# basic_micro.net
KiCad netlist of a schematic drawn in EAGLE
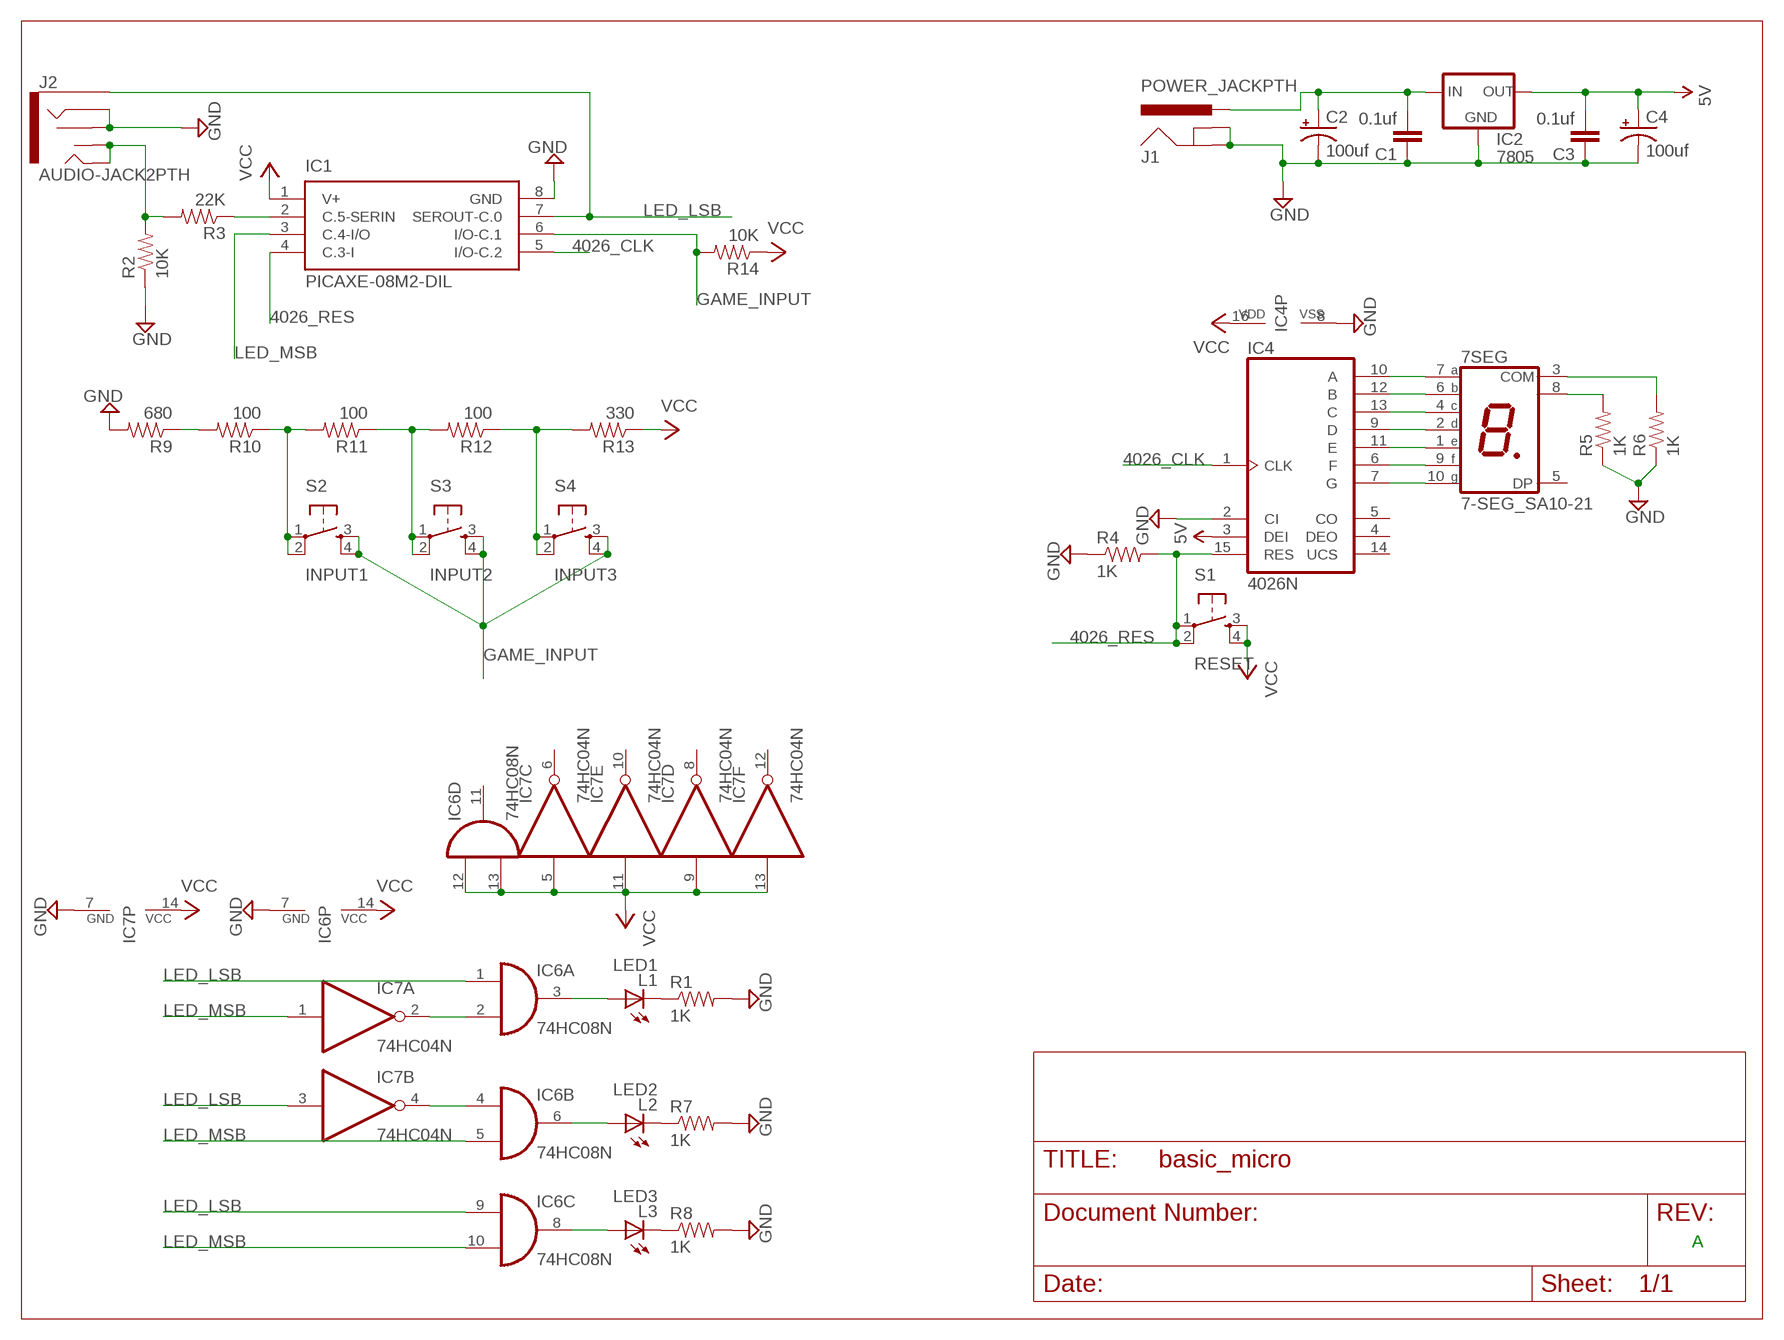
[diagram p0: schematic, sheet 1]

(export (version "E")
  (design (tool "Eeschema 10.0.6"))
  (components
    (comp (ref "7SEG")
      (value "7-SEG_SA10-21")
      (footprint "eagle-import:SA10-21")
      (libsource (lib "eagle-import") (part "7-SEG_SA10-21"))
    )
    (comp (ref "C1")
      (value "0.1uf")
      (footprint "eagle-import:C025-025X050")
      (libsource (lib "eagle-import") (part "C-EU025-025X050"))
    )
    (comp (ref "C2")
      (value "100uf")
      (footprint "eagle-import:ETR3")
      (libsource (lib "eagle-import") (part "CPOL-USETR3"))
    )
    (comp (ref "C3")
      (value "0.1uf")
      (footprint "eagle-import:C025-025X050")
      (libsource (lib "eagle-import") (part "C-EU025-025X050"))
    )
    (comp (ref "C4")
      (value "100uf")
      (footprint "eagle-import:ETR3")
      (libsource (lib "eagle-import") (part "CPOL-USETR3"))
    )
    (comp (ref "IC1")
      (value "PICAXE-08M2-DIL")
      (footprint "eagle-import:DIL8")
      (libsource (lib "eagle-import") (part "PICAXE-08M2-DIL"))
    )
    (comp (ref "IC2")
      (value "7805")
      (footprint "eagle-import:78XXL")
      (libsource (lib "eagle-import") (part "78XXL"))
    )
    (comp (ref "IC4")
      (value "4026N")
      (footprint "eagle-import:DIL16")
      (libsource (lib "eagle-import") (part "4026N"))
    )
    (comp (ref "IC6")
      (value "74HC08N")
      (footprint "eagle-import:DIL14")
      (libsource (lib "eagle-import") (part "7408NHC"))
    )
    (comp (ref "IC7")
      (value "74HC04N")
      (footprint "eagle-import:DIL14")
      (libsource (lib "eagle-import") (part "7404NHC"))
    )
    (comp (ref "J1")
      (value "POWER_JACKPTH")
      (footprint "eagle-import:POWER_JACK_PTH")
      (libsource (lib "eagle-import") (part "POWER_JACKPTH"))
    )
    (comp (ref "J2")
      (value "AUDIO-JACK2PTH")
      (footprint "eagle-import:AUDIO-JACK")
      (libsource (lib "eagle-import") (part "AUDIO-JACK2PTH"))
    )
    (comp (ref "L1")
      (value "LED1")
      (footprint "eagle-import:LED3MM")
      (libsource (lib "eagle-import") (part "LED3MM"))
    )
    (comp (ref "L2")
      (value "LED2")
      (footprint "eagle-import:LED3MM")
      (libsource (lib "eagle-import") (part "LED3MM"))
    )
    (comp (ref "L3")
      (value "LED3")
      (footprint "eagle-import:LED3MM")
      (libsource (lib "eagle-import") (part "LED3MM"))
    )
    (comp (ref "R1")
      (value "1K")
      (footprint "eagle-import:AXIAL-0.4")
      (libsource (lib "eagle-import") (part "RESISTORPTH-1/4W"))
    )
    (comp (ref "R2")
      (value "10K")
      (footprint "eagle-import:AXIAL-0.4")
      (libsource (lib "eagle-import") (part "RESISTORPTH-1/4W"))
    )
    (comp (ref "R3")
      (value "22K")
      (footprint "eagle-import:AXIAL-0.4")
      (libsource (lib "eagle-import") (part "RESISTORPTH-1/4W"))
    )
    (comp (ref "R4")
      (value "1K")
      (footprint "eagle-import:AXIAL-0.4")
      (libsource (lib "eagle-import") (part "RESISTORPTH-1/4W"))
    )
    (comp (ref "R5")
      (value "1K")
      (footprint "eagle-import:AXIAL-0.4")
      (libsource (lib "eagle-import") (part "RESISTORPTH-1/4W"))
    )
    (comp (ref "R6")
      (value "1K")
      (footprint "eagle-import:AXIAL-0.4")
      (libsource (lib "eagle-import") (part "RESISTORPTH-1/4W"))
    )
    (comp (ref "R7")
      (value "1K")
      (footprint "eagle-import:AXIAL-0.4")
      (libsource (lib "eagle-import") (part "RESISTORPTH-1/4W"))
    )
    (comp (ref "R8")
      (value "1K")
      (footprint "eagle-import:AXIAL-0.4")
      (libsource (lib "eagle-import") (part "RESISTORPTH-1/4W"))
    )
    (comp (ref "R9")
      (value "680")
      (footprint "eagle-import:AXIAL-0.4")
      (libsource (lib "eagle-import") (part "RESISTORPTH-1/4W"))
    )
    (comp (ref "R10")
      (value "100")
      (footprint "eagle-import:AXIAL-0.4")
      (libsource (lib "eagle-import") (part "RESISTORPTH-1/4W"))
    )
    (comp (ref "R11")
      (value "100")
      (footprint "eagle-import:AXIAL-0.4")
      (libsource (lib "eagle-import") (part "RESISTORPTH-1/4W"))
    )
    (comp (ref "R12")
      (value "100")
      (footprint "eagle-import:AXIAL-0.4")
      (libsource (lib "eagle-import") (part "RESISTORPTH-1/4W"))
    )
    (comp (ref "R13")
      (value "330")
      (footprint "eagle-import:AXIAL-0.4")
      (libsource (lib "eagle-import") (part "RESISTORPTH-1/4W"))
    )
    (comp (ref "R14")
      (value "10K")
      (footprint "eagle-import:AXIAL-0.4")
      (libsource (lib "eagle-import") (part "RESISTORPTH-1/4W"))
    )
    (comp (ref "S1")
      (value "RESET")
      (footprint "eagle-import:TACTILE-PTH")
      (libsource (lib "eagle-import") (part "TAC_SWITCHPTH"))
    )
    (comp (ref "S2")
      (value "INPUT1")
      (footprint "eagle-import:TACTILE-PTH")
      (libsource (lib "eagle-import") (part "TAC_SWITCHPTH"))
    )
    (comp (ref "S3")
      (value "INPUT2")
      (footprint "eagle-import:TACTILE-PTH")
      (libsource (lib "eagle-import") (part "TAC_SWITCHPTH"))
    )
    (comp (ref "S4")
      (value "INPUT3")
      (footprint "eagle-import:TACTILE-PTH")
      (libsource (lib "eagle-import") (part "TAC_SWITCHPTH"))
    )
  )
  (nets
    (net (code "1") (name "/4026_CLK") (class "Default")
      (node (ref "IC1") (pin "5") (pinfunction "I/O-C.2_5") (pintype "bidirectional"))
      (node (ref "IC4") (pin "1") (pinfunction "CLK_1") (pintype "input"))
    )
    (net (code "2") (name "/4026_RES") (class "Default")
      (node (ref "IC1") (pin "4") (pinfunction "C.3-I_4") (pintype "input"))
      (node (ref "IC4") (pin "15") (pinfunction "RES_15") (pintype "input"))
      (node (ref "R4") (pin "P$2") (pinfunction "2_P$2") (pintype "passive"))
      (node (ref "S1") (pin "1") (pinfunction "1_1") (pintype "passive"))
      (node (ref "S1") (pin "2") (pinfunction "2_2") (pintype "passive"))
    )
    (net (code "3") (name "/GAME_INPUT") (class "Default")
      (node (ref "IC1") (pin "6") (pinfunction "I/O-C.1_6") (pintype "bidirectional"))
      (node (ref "R14") (pin "P$2") (pinfunction "2_P$2") (pintype "passive"))
      (node (ref "S2") (pin "3") (pinfunction "3_3") (pintype "passive"))
      (node (ref "S2") (pin "4") (pinfunction "4_4") (pintype "passive"))
      (node (ref "S3") (pin "3") (pinfunction "3_3") (pintype "passive"))
      (node (ref "S3") (pin "4") (pinfunction "4_4") (pintype "passive"))
      (node (ref "S4") (pin "3") (pinfunction "3_3") (pintype "passive"))
      (node (ref "S4") (pin "4") (pinfunction "4_4") (pintype "passive"))
    )
    (net (code "4") (name "/LED_LSB") (class "Default")
      (node (ref "IC1") (pin "7") (pinfunction "SEROUT-C.0_7") (pintype "output"))
      (node (ref "IC6") (pin "1") (pinfunction "I0_1") (pintype "input"))
      (node (ref "IC6") (pin "9") (pinfunction "I0_9") (pintype "input"))
      (node (ref "IC7") (pin "3") (pinfunction "I_3") (pintype "input"))
      (node (ref "J2") (pin "SLEEVE") (pinfunction "SLEEVE_SLEEVE") (pintype "bidirectional"))
    )
    (net (code "5") (name "/LED_MSB") (class "Default")
      (node (ref "IC1") (pin "3") (pinfunction "C.4-I/O_3") (pintype "bidirectional"))
      (node (ref "IC6") (pin "10") (pinfunction "I1_10") (pintype "input"))
      (node (ref "IC6") (pin "5") (pinfunction "I1_5") (pintype "input"))
      (node (ref "IC7") (pin "1") (pinfunction "I_1") (pintype "input"))
    )
    (net (code "6") (name "5V") (class "Default")
      (node (ref "C3") (pin "2") (pinfunction "2_2") (pintype "passive"))
      (node (ref "C4") (pin "+") (pinfunction "+_+") (pintype "passive"))
      (node (ref "IC2") (pin "OUT") (pinfunction "OUT_OUT") (pintype "passive"))
      (node (ref "IC4") (pin "3") (pinfunction "DEI_3") (pintype "input"))
    )
    (net (code "7") (name "GND") (class "Default")
      (node (ref "C1") (pin "1") (pinfunction "1_1") (pintype "passive"))
      (node (ref "C2") (pin "-") (pinfunction "-_-") (pintype "passive"))
      (node (ref "C3") (pin "1") (pinfunction "1_1") (pintype "passive"))
      (node (ref "C4") (pin "-") (pinfunction "-_-") (pintype "passive"))
      (node (ref "IC1") (pin "8") (pinfunction "GND_8") (pintype "power_in"))
      (node (ref "IC2") (pin "GND") (pinfunction "GND_GND") (pintype "input"))
      (node (ref "IC4") (pin "2") (pinfunction "CI_2") (pintype "input"))
      (node (ref "IC4") (pin "8") (pinfunction "VSS_8") (pintype "power_in"))
      (node (ref "IC6") (pin "7") (pinfunction "GND_7") (pintype "power_in"))
      (node (ref "IC7") (pin "7") (pinfunction "GND_7") (pintype "power_in"))
      (node (ref "J1") (pin "GND") (pinfunction "GND_GND") (pintype "bidirectional"))
      (node (ref "J1") (pin "GNDBREAK") (pinfunction "GNDBREAK_GNDBREAK") (pintype "bidirectional"))
      (node (ref "J2") (pin "RING") (pinfunction "RING_RING") (pintype "bidirectional"))
      (node (ref "J2") (pin "RSH") (pinfunction "RSH_RSH") (pintype "bidirectional"))
      (node (ref "R1") (pin "P$2") (pinfunction "2_P$2") (pintype "passive"))
      (node (ref "R2") (pin "P$1") (pinfunction "1_P$1") (pintype "passive"))
      (node (ref "R4") (pin "P$1") (pinfunction "1_P$1") (pintype "passive"))
      (node (ref "R5") (pin "P$1") (pinfunction "1_P$1") (pintype "passive"))
      (node (ref "R6") (pin "P$1") (pinfunction "1_P$1") (pintype "passive"))
      (node (ref "R7") (pin "P$2") (pinfunction "2_P$2") (pintype "passive"))
      (node (ref "R8") (pin "P$2") (pinfunction "2_P$2") (pintype "passive"))
      (node (ref "R9") (pin "P$2") (pinfunction "2_P$2") (pintype "passive"))
    )
    (net (code "8") (name "Net-(7SEG-A)") (class "Default")
      (node (ref "7SEG") (pin "7") (pinfunction "A_7") (pintype "passive"))
      (node (ref "IC4") (pin "10") (pinfunction "A_10") (pintype "output"))
    )
    (net (code "9") (name "Net-(7SEG-B)") (class "Default")
      (node (ref "7SEG") (pin "6") (pinfunction "B_6") (pintype "passive"))
      (node (ref "IC4") (pin "12") (pinfunction "B_12") (pintype "output"))
    )
    (net (code "10") (name "Net-(7SEG-C)") (class "Default")
      (node (ref "7SEG") (pin "4") (pinfunction "C_4") (pintype "passive"))
      (node (ref "IC4") (pin "13") (pinfunction "C_13") (pintype "output"))
    )
    (net (code "11") (name "Net-(7SEG-D)") (class "Default")
      (node (ref "7SEG") (pin "2") (pinfunction "D_2") (pintype "passive"))
      (node (ref "IC4") (pin "9") (pinfunction "D_9") (pintype "output"))
    )
    (net (code "12") (name "Net-(7SEG-E)") (class "Default")
      (node (ref "7SEG") (pin "1") (pinfunction "E_1") (pintype "passive"))
      (node (ref "IC4") (pin "11") (pinfunction "E_11") (pintype "output"))
    )
    (net (code "13") (name "Net-(7SEG-F)") (class "Default")
      (node (ref "7SEG") (pin "9") (pinfunction "F_9") (pintype "passive"))
      (node (ref "IC4") (pin "6") (pinfunction "F_6") (pintype "output"))
    )
    (net (code "14") (name "Net-(7SEG-G)") (class "Default")
      (node (ref "7SEG") (pin "10") (pinfunction "G_10") (pintype "passive"))
      (node (ref "IC4") (pin "7") (pinfunction "G_7") (pintype "output"))
    )
    (net (code "15") (name "Net-(C1-Pad2)") (class "Default")
      (node (ref "C1") (pin "2") (pinfunction "2_2") (pintype "passive"))
      (node (ref "C2") (pin "+") (pinfunction "+_+") (pintype "passive"))
      (node (ref "IC2") (pin "IN") (pinfunction "IN_IN") (pintype "input"))
      (node (ref "J1") (pin "PWR") (pinfunction "PWR_PWR") (pintype "bidirectional"))
    )
    (net (code "16") (name "Net-(IC1-C.5-SERIN)") (class "Default")
      (node (ref "IC1") (pin "2") (pinfunction "C.5-SERIN_2") (pintype "input"))
      (node (ref "R3") (pin "P$1") (pinfunction "1_P$1") (pintype "passive"))
    )
    (net (code "17") (name "Net-(IC6A-I1)") (class "Default")
      (node (ref "IC6") (pin "2") (pinfunction "I1_2") (pintype "input"))
      (node (ref "IC7") (pin "2") (pinfunction "O_2") (pintype "output"))
    )
    (net (code "18") (name "Net-(IC6A-O)") (class "Default")
      (node (ref "IC6") (pin "3") (pinfunction "O_3") (pintype "output"))
      (node (ref "L1") (pin "A") (pinfunction "A_A") (pintype "passive"))
    )
    (net (code "19") (name "Net-(IC6B-I0)") (class "Default")
      (node (ref "IC6") (pin "4") (pinfunction "I0_4") (pintype "input"))
      (node (ref "IC7") (pin "4") (pinfunction "O_4") (pintype "output"))
    )
    (net (code "20") (name "Net-(IC6B-O)") (class "Default")
      (node (ref "IC6") (pin "6") (pinfunction "O_6") (pintype "output"))
      (node (ref "L2") (pin "A") (pinfunction "A_A") (pintype "passive"))
    )
    (net (code "21") (name "Net-(IC6C-O)") (class "Default")
      (node (ref "IC6") (pin "8") (pinfunction "O_8") (pintype "output"))
      (node (ref "L3") (pin "A") (pinfunction "A_A") (pintype "passive"))
    )
    (net (code "22") (name "Net-(L1-C)") (class "Default")
      (node (ref "L1") (pin "K") (pinfunction "C_K") (pintype "passive"))
      (node (ref "R1") (pin "P$1") (pinfunction "1_P$1") (pintype "passive"))
    )
    (net (code "23") (name "Net-(L2-C)") (class "Default")
      (node (ref "L2") (pin "K") (pinfunction "C_K") (pintype "passive"))
      (node (ref "R7") (pin "P$1") (pinfunction "1_P$1") (pintype "passive"))
    )
    (net (code "24") (name "Net-(L3-C)") (class "Default")
      (node (ref "L3") (pin "K") (pinfunction "C_K") (pintype "passive"))
      (node (ref "R8") (pin "P$1") (pinfunction "1_P$1") (pintype "passive"))
    )
    (net (code "25") (name "Net-(R2-2)") (class "Default")
      (node (ref "J2") (pin "TIP") (pinfunction "TIP_TIP") (pintype "bidirectional"))
      (node (ref "J2") (pin "TSH") (pinfunction "TSH_TSH") (pintype "bidirectional"))
      (node (ref "R2") (pin "P$2") (pinfunction "2_P$2") (pintype "passive"))
      (node (ref "R3") (pin "P$2") (pinfunction "2_P$2") (pintype "passive"))
    )
    (net (code "26") (name "Net-(R5-2)") (class "Default")
      (node (ref "7SEG") (pin "8") (pinfunction "COM_8") (pintype "passive"))
      (node (ref "R5") (pin "P$2") (pinfunction "2_P$2") (pintype "passive"))
    )
    (net (code "27") (name "Net-(R6-2)") (class "Default")
      (node (ref "7SEG") (pin "3") (pinfunction "COM_3") (pintype "passive"))
      (node (ref "R6") (pin "P$2") (pinfunction "2_P$2") (pintype "passive"))
    )
    (net (code "28") (name "Net-(R10-1)") (class "Default")
      (node (ref "R10") (pin "P$1") (pinfunction "1_P$1") (pintype "passive"))
      (node (ref "R11") (pin "P$2") (pinfunction "2_P$2") (pintype "passive"))
      (node (ref "S2") (pin "1") (pinfunction "1_1") (pintype "passive"))
      (node (ref "S2") (pin "2") (pinfunction "2_2") (pintype "passive"))
    )
    (net (code "29") (name "Net-(R10-2)") (class "Default")
      (node (ref "R10") (pin "P$2") (pinfunction "2_P$2") (pintype "passive"))
      (node (ref "R9") (pin "P$1") (pinfunction "1_P$1") (pintype "passive"))
    )
    (net (code "30") (name "Net-(R11-1)") (class "Default")
      (node (ref "R11") (pin "P$1") (pinfunction "1_P$1") (pintype "passive"))
      (node (ref "R12") (pin "P$2") (pinfunction "2_P$2") (pintype "passive"))
      (node (ref "S3") (pin "1") (pinfunction "1_1") (pintype "passive"))
      (node (ref "S3") (pin "2") (pinfunction "2_2") (pintype "passive"))
    )
    (net (code "31") (name "Net-(R12-1)") (class "Default")
      (node (ref "R12") (pin "P$1") (pinfunction "1_P$1") (pintype "passive"))
      (node (ref "R13") (pin "P$2") (pinfunction "2_P$2") (pintype "passive"))
      (node (ref "S4") (pin "1") (pinfunction "1_1") (pintype "passive"))
      (node (ref "S4") (pin "2") (pinfunction "2_2") (pintype "passive"))
    )
    (net (code "32") (name "VCC") (class "Default")
      (node (ref "IC1") (pin "1") (pinfunction "V+_1") (pintype "power_in"))
      (node (ref "IC4") (pin "16") (pinfunction "VDD_16") (pintype "power_in"))
      (node (ref "IC6") (pin "12") (pinfunction "I0_12") (pintype "input"))
      (node (ref "IC6") (pin "13") (pinfunction "I1_13") (pintype "input"))
      (node (ref "IC6") (pin "14") (pinfunction "VCC_14") (pintype "power_in"))
      (node (ref "IC7") (pin "11") (pinfunction "I_11") (pintype "input"))
      (node (ref "IC7") (pin "13") (pinfunction "I_13") (pintype "input"))
      (node (ref "IC7") (pin "14") (pinfunction "VCC_14") (pintype "power_in"))
      (node (ref "IC7") (pin "5") (pinfunction "I_5") (pintype "input"))
      (node (ref "IC7") (pin "9") (pinfunction "I_9") (pintype "input"))
      (node (ref "R13") (pin "P$1") (pinfunction "1_P$1") (pintype "passive"))
      (node (ref "R14") (pin "P$1") (pinfunction "1_P$1") (pintype "passive"))
      (node (ref "S1") (pin "3") (pinfunction "3_3") (pintype "passive"))
      (node (ref "S1") (pin "4") (pinfunction "4_4") (pintype "passive"))
    )
    (net (code "33") (name "unconnected-(7SEG-DP-Pad5)") (class "Default")
      (node (ref "7SEG") (pin "5") (pinfunction "DP_5") (pintype "passive"))
    )
    (net (code "34") (name "unconnected-(IC4A-CO-Pad5)") (class "Default")
      (node (ref "IC4") (pin "5") (pinfunction "CO_5") (pintype "output"))
    )
    (net (code "35") (name "unconnected-(IC4A-DEO-Pad4)") (class "Default")
      (node (ref "IC4") (pin "4") (pinfunction "DEO_4") (pintype "output"))
    )
    (net (code "36") (name "unconnected-(IC4A-UCS-Pad14)") (class "Default")
      (node (ref "IC4") (pin "14") (pinfunction "UCS_14") (pintype "output"))
    )
    (net (code "37") (name "unconnected-(IC6D-O-Pad11)") (class "Default")
      (node (ref "IC6") (pin "11") (pinfunction "O_11") (pintype "output"))
    )
    (net (code "38") (name "unconnected-(IC7C-O-Pad6)") (class "Default")
      (node (ref "IC7") (pin "6") (pinfunction "O_6") (pintype "output"))
    )
    (net (code "39") (name "unconnected-(IC7D-O-Pad8)") (class "Default")
      (node (ref "IC7") (pin "8") (pinfunction "O_8") (pintype "output"))
    )
    (net (code "40") (name "unconnected-(IC7E-O-Pad10)") (class "Default")
      (node (ref "IC7") (pin "10") (pinfunction "O_10") (pintype "output"))
    )
    (net (code "41") (name "unconnected-(IC7F-O-Pad12)") (class "Default")
      (node (ref "IC7") (pin "12") (pinfunction "O_12") (pintype "output"))
    )
  )
)
